# IS25LP128_Breakout_PCB.net
KiCad netlist of a schematic drawn in Altium Designer
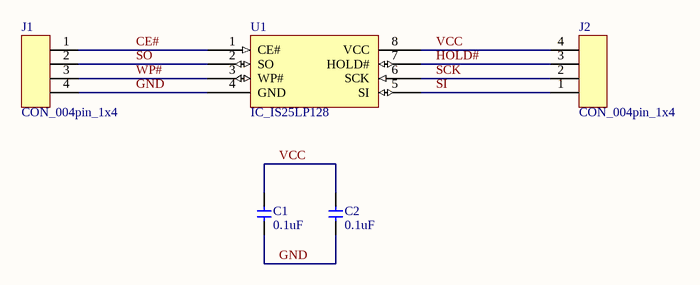
[diagram p0: IS25LP128_Breakout_PCB.SchDoc]

(export (version "E")
  (design (tool "Eeschema 10.0.6"))
  (components
    (comp (ref "C1")
      (value "0.1uF")
      (footprint "0603")
      (description "Capacitor generic")
      (libsource (lib "BWRC") (part "DISCRETE_C"))
    )
    (comp (ref "C2")
      (value "0.1uF")
      (footprint "0603")
      (description "Capacitor generic")
      (libsource (lib "BWRC") (part "DISCRETE_C"))
    )
    (comp (ref "J1")
      (value "CON_004pin_1x4")
      (footprint "CON-004-100-400X100/1X4-POST")
      (description "Con 4 pins 1x4")
      (libsource (lib "") (part "CON_004pin_1x4_1"))
    )
    (comp (ref "J2")
      (value "CON_004pin_1x4")
      (footprint "CON-004-100-400X100/1X4-POST")
      (description "Con 4 pins 1x4")
      (libsource (lib "BWRC") (part "CON_004pin_1x4"))
    )
    (comp (ref "U1")
      (value "IC_IS25LP128")
      (footprint "GW-08-1.27-5.2X8.0")
      (libsource (lib "BWRC") (part "IC_IS25LP128"))
    )
  )
  (nets
    (net (code "1") (name "/CE#") (class "Default")
      (node (ref "J1") (pin "1") (pinfunction "1_1") (pintype "passive"))
      (node (ref "U1") (pin "1") (pinfunction "CE#_1") (pintype "input"))
    )
    (net (code "2") (name "/GND") (class "Default")
      (node (ref "C1") (pin "2") (pinfunction "2_2") (pintype "passive"))
      (node (ref "C2") (pin "2") (pinfunction "2_2") (pintype "passive"))
      (node (ref "J1") (pin "4") (pinfunction "4_4") (pintype "passive"))
      (node (ref "U1") (pin "4") (pinfunction "GND_4") (pintype "power_in"))
    )
    (net (code "3") (name "/HOLD#") (class "Default")
      (node (ref "J2") (pin "3") (pinfunction "3_3") (pintype "passive"))
      (node (ref "U1") (pin "7") (pinfunction "HOLD#_7") (pintype "bidirectional"))
    )
    (net (code "4") (name "/SCK") (class "Default")
      (node (ref "J2") (pin "2") (pinfunction "2_2") (pintype "passive"))
      (node (ref "U1") (pin "6") (pinfunction "SCK_6") (pintype "input"))
    )
    (net (code "5") (name "/SI") (class "Default")
      (node (ref "J2") (pin "1") (pinfunction "1_1") (pintype "passive"))
      (node (ref "U1") (pin "5") (pinfunction "SI_5") (pintype "bidirectional"))
    )
    (net (code "6") (name "/SO") (class "Default")
      (node (ref "J1") (pin "2") (pinfunction "2_2") (pintype "passive"))
      (node (ref "U1") (pin "2") (pinfunction "SO_2") (pintype "bidirectional"))
    )
    (net (code "7") (name "/VCC") (class "Default")
      (node (ref "C1") (pin "1") (pinfunction "1_1") (pintype "passive"))
      (node (ref "C2") (pin "1") (pinfunction "1_1") (pintype "passive"))
      (node (ref "J2") (pin "4") (pinfunction "4_4") (pintype "passive"))
      (node (ref "U1") (pin "8") (pinfunction "VCC_8") (pintype "power_in"))
    )
    (net (code "8") (name "/WP#") (class "Default")
      (node (ref "J1") (pin "3") (pinfunction "3_3") (pintype "passive"))
      (node (ref "U1") (pin "3") (pinfunction "WP#_3") (pintype "bidirectional"))
    )
  )
)
